# AVR-USB-Downloader.net
KiCad netlist of a schematic drawn in EAGLE
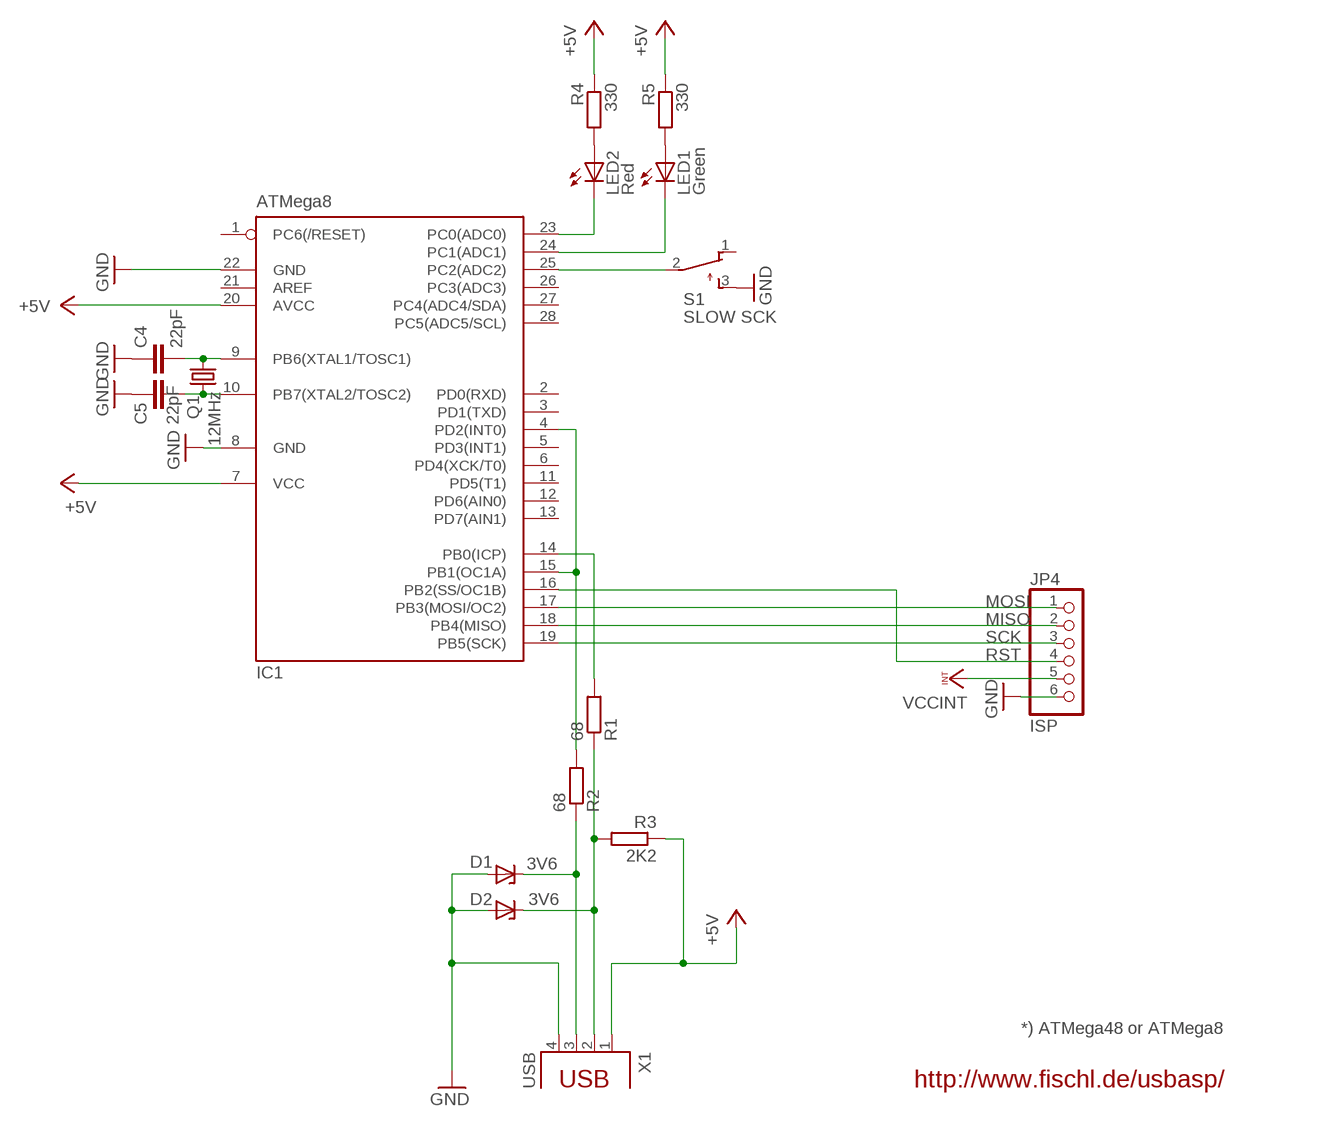
[diagram p0: schematic, sheet 1]

(export (version "E")
  (design (tool "Eeschema 10.0.6"))
  (components
    (comp (ref "C4")
      (value "22pF")
      (footprint "eagle-import:C025-024X044")
      (libsource (lib "eagle-import") (part "C-EU025-024X044"))
    )
    (comp (ref "C5")
      (value "22pF")
      (footprint "eagle-import:C025-024X044")
      (libsource (lib "eagle-import") (part "C-EU025-024X044"))
    )
    (comp (ref "D1")
      (value "3V6")
      (footprint "eagle-import:DO34Z7")
      (libsource (lib "eagle-import") (part "ZENER-DIODEDO34-7"))
    )
    (comp (ref "D2")
      (value "3V6")
      (footprint "eagle-import:DO34Z7")
      (libsource (lib "eagle-import") (part "ZENER-DIODEDO34-7"))
    )
    (comp (ref "IC1")
      (value "ATMega8")
      (footprint "eagle-import:DIL28-3")
      (libsource (lib "eagle-import") (part "MEGA8-P"))
    )
    (comp (ref "JP4")
      (value "ISP")
      (footprint "eagle-import:1X06")
      (libsource (lib "eagle-import") (part "PINHD-1X6"))
    )
    (comp (ref "LED1")
      (value "Green")
      (footprint "eagle-import:LED3MM")
      (libsource (lib "eagle-import") (part "LED3MM"))
    )
    (comp (ref "LED2")
      (value "Red")
      (footprint "eagle-import:LED3MM")
      (libsource (lib "eagle-import") (part "LED3MM"))
    )
    (comp (ref "Q1")
      (value "12MHz")
      (footprint "eagle-import:HC49_S")
      (libsource (lib "eagle-import") (part "CRYTALHC49S"))
    )
    (comp (ref "R1")
      (value "68")
      (footprint "eagle-import:0207_10")
      (libsource (lib "eagle-import") (part "R-EU_0207/10"))
    )
    (comp (ref "R2")
      (value "68")
      (footprint "eagle-import:0207_10")
      (libsource (lib "eagle-import") (part "R-EU_0207/10"))
    )
    (comp (ref "R3")
      (value "2K2")
      (footprint "eagle-import:0207_10")
      (libsource (lib "eagle-import") (part "R-EU_0207/10"))
    )
    (comp (ref "R4")
      (value "330")
      (footprint "eagle-import:0207_10")
      (libsource (lib "eagle-import") (part "R-EU_0207/10"))
    )
    (comp (ref "R5")
      (value "330")
      (footprint "eagle-import:0207_10")
      (libsource (lib "eagle-import") (part "R-EU_0207/10"))
    )
    (comp (ref "S1")
      (value "SLOW SCK")
      (footprint "eagle-import:TL3XPO")
      (libsource (lib "eagle-import") (part "TL32PO"))
    )
    (comp (ref "X1")
      (value "USB")
      (footprint "eagle-import:PN61729")
      (libsource (lib "eagle-import") (part "PN61729"))
    )
  )
  (nets
    (net (code "1") (name "+5V") (class "Default")
      (node (ref "IC1") (pin "20") (pinfunction "AVCC_20") (pintype "power_in"))
      (node (ref "IC1") (pin "7") (pinfunction "VCC_7") (pintype "power_in"))
      (node (ref "R3") (pin "1") (pinfunction "1_1") (pintype "passive"))
      (node (ref "R4") (pin "1") (pinfunction "1_1") (pintype "passive"))
      (node (ref "R5") (pin "1") (pinfunction "1_1") (pintype "passive"))
      (node (ref "X1") (pin "1") (pinfunction "1_1") (pintype "passive"))
    )
    (net (code "2") (name "/MISO") (class "Default")
      (node (ref "IC1") (pin "18") (pinfunction "PB4(MISO)_18") (pintype "bidirectional"))
      (node (ref "JP4") (pin "2") (pinfunction "2_2") (pintype "passive"))
    )
    (net (code "3") (name "/MOSI") (class "Default")
      (node (ref "IC1") (pin "17") (pinfunction "PB3(MOSI/OC2)_17") (pintype "bidirectional"))
      (node (ref "JP4") (pin "1") (pinfunction "1_1") (pintype "passive"))
    )
    (net (code "4") (name "/RST") (class "Default")
      (node (ref "IC1") (pin "16") (pinfunction "PB2(SS/OC1B)_16") (pintype "bidirectional"))
      (node (ref "JP4") (pin "4") (pinfunction "4_4") (pintype "passive"))
    )
    (net (code "5") (name "/SCK") (class "Default")
      (node (ref "IC1") (pin "19") (pinfunction "PB5(SCK)_19") (pintype "bidirectional"))
      (node (ref "JP4") (pin "3") (pinfunction "3_3") (pintype "passive"))
    )
    (net (code "6") (name "GND") (class "Default")
      (node (ref "C4") (pin "1") (pinfunction "1_1") (pintype "passive"))
      (node (ref "C5") (pin "1") (pinfunction "1_1") (pintype "passive"))
      (node (ref "D1") (pin "A") (pinfunction "A_A") (pintype "passive"))
      (node (ref "D2") (pin "A") (pinfunction "A_A") (pintype "passive"))
      (node (ref "IC1") (pin "22") (pinfunction "GND_22") (pintype "power_in"))
      (node (ref "IC1") (pin "8") (pinfunction "GND_8") (pintype "power_in"))
      (node (ref "JP4") (pin "6") (pinfunction "6_6") (pintype "passive"))
      (node (ref "S1") (pin "3") (pinfunction "S_3") (pintype "passive"))
      (node (ref "X1") (pin "4") (pinfunction "4_4") (pintype "passive"))
    )
    (net (code "7") (name "Net-(D1-PadC)") (class "Default")
      (node (ref "D1") (pin "C") (pinfunction "C_C") (pintype "passive"))
      (node (ref "R2") (pin "1") (pinfunction "1_1") (pintype "passive"))
      (node (ref "X1") (pin "3") (pinfunction "3_3") (pintype "passive"))
    )
    (net (code "8") (name "Net-(D2-PadC)") (class "Default")
      (node (ref "D2") (pin "C") (pinfunction "C_C") (pintype "passive"))
      (node (ref "R1") (pin "1") (pinfunction "1_1") (pintype "passive"))
      (node (ref "R3") (pin "2") (pinfunction "2_2") (pintype "passive"))
      (node (ref "X1") (pin "2") (pinfunction "2_2") (pintype "passive"))
    )
    (net (code "9") (name "Net-(IC1-PB0(ICP))") (class "Default")
      (node (ref "IC1") (pin "14") (pinfunction "PB0(ICP)_14") (pintype "bidirectional"))
      (node (ref "R1") (pin "2") (pinfunction "2_2") (pintype "passive"))
    )
    (net (code "10") (name "Net-(IC1-PB1(OC1A))") (class "Default")
      (node (ref "IC1") (pin "15") (pinfunction "PB1(OC1A)_15") (pintype "bidirectional"))
      (node (ref "IC1") (pin "4") (pinfunction "PD2(INT0)_4") (pintype "bidirectional"))
      (node (ref "R2") (pin "2") (pinfunction "2_2") (pintype "passive"))
    )
    (net (code "11") (name "Net-(IC1-PB6(XTAL1{slash}TOSC1))") (class "Default")
      (node (ref "C4") (pin "2") (pinfunction "2_2") (pintype "passive"))
      (node (ref "IC1") (pin "9") (pinfunction "PB6(XTAL1/TOSC1)_9") (pintype "bidirectional"))
      (node (ref "Q1") (pin "2") (pinfunction "2_2") (pintype "passive"))
    )
    (net (code "12") (name "Net-(IC1-PB7(XTAL2{slash}TOSC2))") (class "Default")
      (node (ref "C5") (pin "2") (pinfunction "2_2") (pintype "passive"))
      (node (ref "IC1") (pin "10") (pinfunction "PB7(XTAL2/TOSC2)_10") (pintype "bidirectional"))
      (node (ref "Q1") (pin "1") (pinfunction "1_1") (pintype "passive"))
    )
    (net (code "13") (name "Net-(IC1-PC0(ADC0))") (class "Default")
      (node (ref "IC1") (pin "23") (pinfunction "PC0(ADC0)_23") (pintype "bidirectional"))
      (node (ref "LED2") (pin "K") (pinfunction "C_K") (pintype "passive"))
    )
    (net (code "14") (name "Net-(IC1-PC1(ADC1))") (class "Default")
      (node (ref "IC1") (pin "24") (pinfunction "PC1(ADC1)_24") (pintype "bidirectional"))
      (node (ref "LED1") (pin "K") (pinfunction "C_K") (pintype "passive"))
    )
    (net (code "15") (name "Net-(IC1-PC2(ADC2))") (class "Default")
      (node (ref "IC1") (pin "25") (pinfunction "PC2(ADC2)_25") (pintype "bidirectional"))
      (node (ref "S1") (pin "2") (pinfunction "P_2") (pintype "passive"))
    )
    (net (code "16") (name "Net-(LED1-PadA)") (class "Default")
      (node (ref "LED1") (pin "A") (pinfunction "A_A") (pintype "passive"))
      (node (ref "R5") (pin "2") (pinfunction "2_2") (pintype "passive"))
    )
    (net (code "17") (name "Net-(LED2-PadA)") (class "Default")
      (node (ref "LED2") (pin "A") (pinfunction "A_A") (pintype "passive"))
      (node (ref "R4") (pin "2") (pinfunction "2_2") (pintype "passive"))
    )
    (net (code "18") (name "VCCINT") (class "Default")
      (node (ref "JP4") (pin "5") (pinfunction "5_5") (pintype "passive"))
    )
    (net (code "19") (name "unconnected-(IC1-AREF-Pad21)") (class "Default")
      (node (ref "IC1") (pin "21") (pinfunction "AREF_21") (pintype "passive"))
    )
    (net (code "20") (name "unconnected-(IC1-PC3(ADC3)-Pad26)") (class "Default")
      (node (ref "IC1") (pin "26") (pinfunction "PC3(ADC3)_26") (pintype "bidirectional"))
    )
    (net (code "21") (name "unconnected-(IC1-PC4(ADC4{slash}SDA)-Pad27)") (class "Default")
      (node (ref "IC1") (pin "27") (pinfunction "PC4(ADC4/SDA)_27") (pintype "bidirectional"))
    )
    (net (code "22") (name "unconnected-(IC1-PC5(ADC5{slash}SCL)-Pad28)") (class "Default")
      (node (ref "IC1") (pin "28") (pinfunction "PC5(ADC5/SCL)_28") (pintype "bidirectional"))
    )
    (net (code "23") (name "unconnected-(IC1-PC6({slash}RESET)-Pad1)") (class "Default")
      (node (ref "IC1") (pin "1") (pinfunction "PC6(/RESET)_1") (pintype "bidirectional"))
    )
    (net (code "24") (name "unconnected-(IC1-PD0(RXD)-Pad2)") (class "Default")
      (node (ref "IC1") (pin "2") (pinfunction "PD0(RXD)_2") (pintype "bidirectional"))
    )
    (net (code "25") (name "unconnected-(IC1-PD1(TXD)-Pad3)") (class "Default")
      (node (ref "IC1") (pin "3") (pinfunction "PD1(TXD)_3") (pintype "bidirectional"))
    )
    (net (code "26") (name "unconnected-(IC1-PD3(INT1)-Pad5)") (class "Default")
      (node (ref "IC1") (pin "5") (pinfunction "PD3(INT1)_5") (pintype "bidirectional"))
    )
    (net (code "27") (name "unconnected-(IC1-PD4(XCK{slash}T0)-Pad6)") (class "Default")
      (node (ref "IC1") (pin "6") (pinfunction "PD4(XCK/T0)_6") (pintype "bidirectional"))
    )
    (net (code "28") (name "unconnected-(IC1-PD5(T1)-Pad11)") (class "Default")
      (node (ref "IC1") (pin "11") (pinfunction "PD5(T1)_11") (pintype "bidirectional"))
    )
    (net (code "29") (name "unconnected-(IC1-PD6(AIN0)-Pad12)") (class "Default")
      (node (ref "IC1") (pin "12") (pinfunction "PD6(AIN0)_12") (pintype "bidirectional"))
    )
    (net (code "30") (name "unconnected-(IC1-PD7(AIN1)-Pad13)") (class "Default")
      (node (ref "IC1") (pin "13") (pinfunction "PD7(AIN1)_13") (pintype "bidirectional"))
    )
    (net (code "31") (name "unconnected-(S1-O-Pad1)") (class "Default")
      (node (ref "S1") (pin "1") (pinfunction "O_1") (pintype "passive"))
    )
  )
)
